# InterfaceBoard.net
KiCad netlist of a schematic drawn in Altium Designer
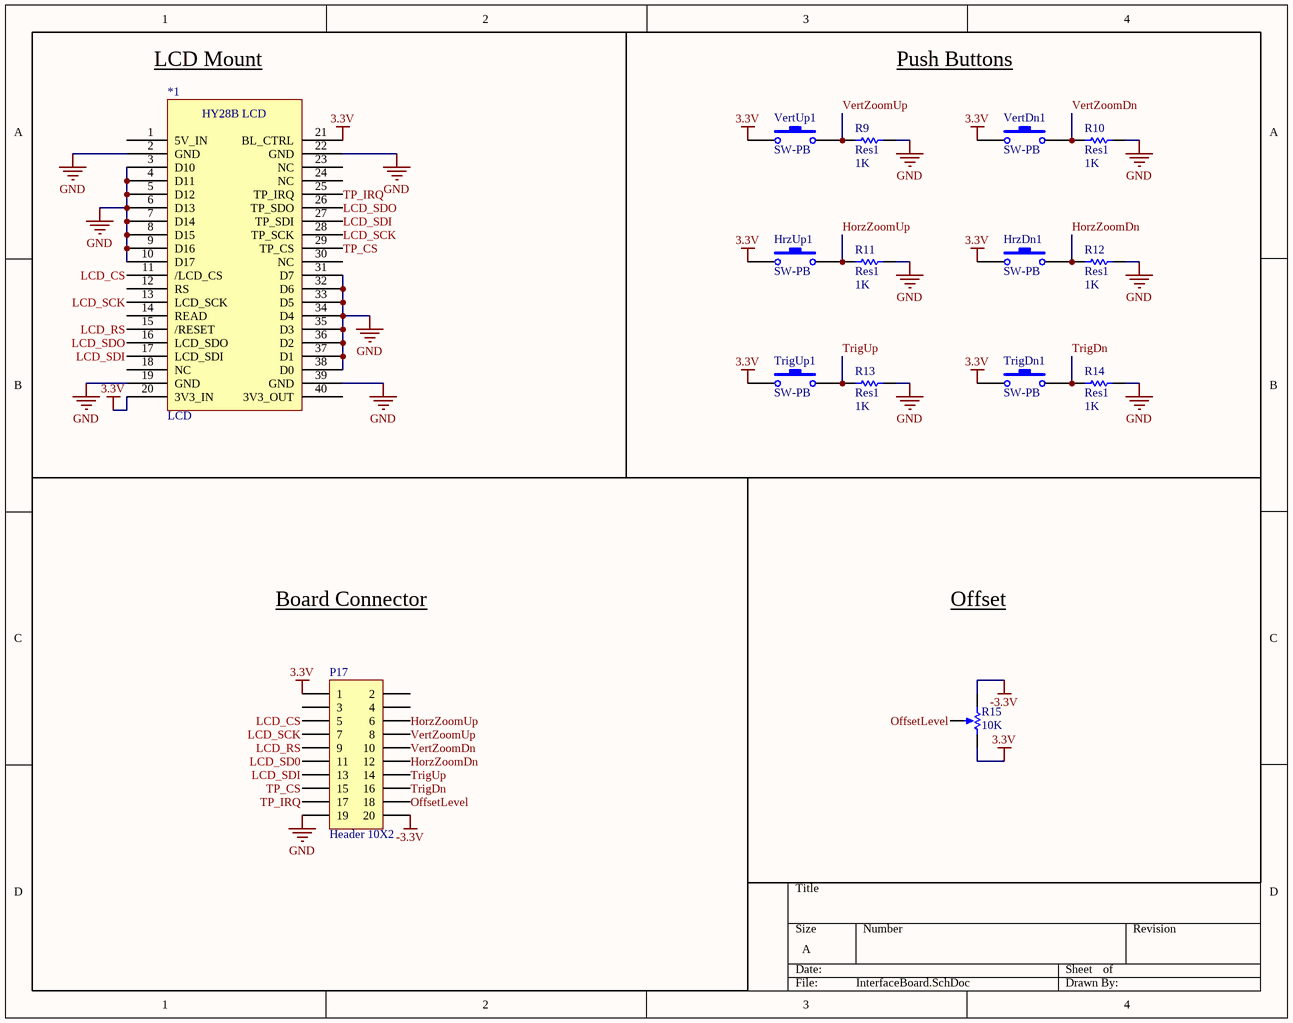
[diagram p0: InterfaceBoard.SchDoc]

(export (version "E")
  (design (tool "Eeschema 10.0.6"))
  (components
    (comp (ref "*1") (value "LCD") (footprint "LCD Footprint") (libsource (lib "MySchematics") (part "LCD")))
    (comp (ref "HrzDn1")
      (value "SW-PB")
      (footprint "SW PB")
      (description "DIGIKEY SW400-ND")
      (fields (field (name "PUBLISHER") "Altium Limited"))
      (libsource (lib "ECE LIB new") (part "SW-PB"))
    )
    (comp (ref "HrzUp1")
      (value "SW-PB")
      (footprint "SW PB")
      (description "DIGIKEY SW400-ND")
      (fields (field (name "PUBLISHER") "Altium Limited"))
      (libsource (lib "ECE LIB new") (part "SW-PB"))
    )
    (comp (ref "P17")
      (value "Header 10X2")
      (footprint "HDR2X10")
      (description "Header, 10-Pin, Dual row")
      (fields (field (name "PUBLISHER") "Altium Limited"))
      (libsource (lib "Miscellaneous Connectors") (part "Header 10X2"))
    )
    (comp (ref "R9")
      (value "Res1")
      (footprint "AXIAL-0.3")
      (description "Resistor")
      (fields (field (name "ALTIUM_VALUE") "1K") (field (name "PUBLISHER") "Altium Limited"))
      (libsource (lib "Miscellaneous Devices") (part "Res1"))
    )
    (comp (ref "R10")
      (value "Res1")
      (footprint "AXIAL-0.3")
      (description "Resistor")
      (fields (field (name "ALTIUM_VALUE") "1K") (field (name "PUBLISHER") "Altium Limited"))
      (libsource (lib "Miscellaneous Devices") (part "Res1"))
    )
    (comp (ref "R11")
      (value "Res1")
      (footprint "AXIAL-0.3")
      (description "Resistor")
      (fields (field (name "ALTIUM_VALUE") "1K") (field (name "PUBLISHER") "Altium Limited"))
      (libsource (lib "Miscellaneous Devices") (part "Res1"))
    )
    (comp (ref "R12")
      (value "Res1")
      (footprint "AXIAL-0.3")
      (description "Resistor")
      (fields (field (name "ALTIUM_VALUE") "1K") (field (name "PUBLISHER") "Altium Limited"))
      (libsource (lib "Miscellaneous Devices") (part "Res1"))
    )
    (comp (ref "R13")
      (value "Res1")
      (footprint "AXIAL-0.3")
      (description "Resistor")
      (fields (field (name "ALTIUM_VALUE") "1K") (field (name "PUBLISHER") "Altium Limited"))
      (libsource (lib "Miscellaneous Devices") (part "Res1"))
    )
    (comp (ref "R14")
      (value "Res1")
      (footprint "AXIAL-0.3")
      (description "Resistor")
      (fields (field (name "ALTIUM_VALUE") "1K") (field (name "PUBLISHER") "Altium Limited"))
      (libsource (lib "Miscellaneous Devices") (part "Res1"))
    )
    (comp (ref "R15")
      (value "10K")
      (footprint "BigPot")
      (description "Potentiometer")
      (fields (field (name "Comment") "RPot_3") (field (name "PUBLISHER") "Altium Limited"))
      (libsource (lib "ECE LIB new") (part "RPot"))
    )
    (comp (ref "TrigDn1")
      (value "SW-PB")
      (footprint "SW PB")
      (description "DIGIKEY SW400-ND")
      (fields (field (name "PUBLISHER") "Altium Limited"))
      (libsource (lib "ECE LIB new") (part "SW-PB"))
    )
    (comp (ref "TrigUp1")
      (value "SW-PB")
      (footprint "SW PB")
      (description "DIGIKEY SW400-ND")
      (fields (field (name "PUBLISHER") "Altium Limited"))
      (libsource (lib "ECE LIB new") (part "SW-PB"))
    )
    (comp (ref "VertDn1")
      (value "SW-PB")
      (footprint "SW PB")
      (description "DIGIKEY SW400-ND")
      (fields (field (name "PUBLISHER") "Altium Limited"))
      (libsource (lib "ECE LIB new") (part "SW-PB"))
    )
    (comp (ref "VertUp1")
      (value "SW-PB")
      (footprint "SW PB")
      (description "DIGIKEY SW400-ND")
      (fields (field (name "PUBLISHER") "Altium Limited"))
      (libsource (lib "ECE LIB new") (part "SW-PB"))
    )
  )
  (nets
    (net (code "1") (name "-3.3V") (class "Default")
      (node (ref "P17") (pin "20") (pinfunction "20_20") (pintype "passive"))
      (node (ref "R15") (pin "1") (pinfunction "TOP_1") (pintype "passive"))
    )
    (net (code "2") (name "/HorzZoomDn") (class "Default")
      (node (ref "HrzDn1") (pin "2") (pinfunction "2_2") (pintype "passive"))
      (node (ref "P17") (pin "12") (pinfunction "12_12") (pintype "passive"))
      (node (ref "R12") (pin "1") (pinfunction "1_1") (pintype "passive"))
    )
    (net (code "3") (name "/HorzZoomUp") (class "Default")
      (node (ref "HrzUp1") (pin "2") (pinfunction "2_2") (pintype "passive"))
      (node (ref "P17") (pin "6") (pinfunction "6_6") (pintype "passive"))
      (node (ref "R11") (pin "1") (pinfunction "1_1") (pintype "passive"))
    )
    (net (code "4") (name "/LCD_CS") (class "Default")
      (node (ref "*1") (pin "11") (pinfunction "/LCD_CS_11") (pintype "passive"))
      (node (ref "P17") (pin "5") (pinfunction "5_5") (pintype "passive"))
    )
    (net (code "5") (name "/LCD_RS") (class "Default")
      (node (ref "*1") (pin "15") (pinfunction "/RESET_15") (pintype "passive"))
      (node (ref "P17") (pin "9") (pinfunction "9_9") (pintype "passive"))
    )
    (net (code "6") (name "/LCD_SCK") (class "Default")
      (node (ref "*1") (pin "13") (pinfunction "LCD_SCK_13") (pintype "passive"))
      (node (ref "*1") (pin "28") (pinfunction "TP_SCK_28") (pintype "passive"))
      (node (ref "P17") (pin "7") (pinfunction "7_7") (pintype "passive"))
    )
    (net (code "7") (name "/LCD_SD0") (class "Default")
      (node (ref "P17") (pin "11") (pinfunction "11_11") (pintype "passive"))
    )
    (net (code "8") (name "/LCD_SDI") (class "Default")
      (node (ref "*1") (pin "17") (pinfunction "LCD_SDI_17") (pintype "passive"))
      (node (ref "*1") (pin "27") (pinfunction "TP_SDI_27") (pintype "passive"))
      (node (ref "P17") (pin "13") (pinfunction "13_13") (pintype "passive"))
    )
    (net (code "9") (name "/LCD_SDO") (class "Default")
      (node (ref "*1") (pin "16") (pinfunction "LCD_SDO_16") (pintype "passive"))
      (node (ref "*1") (pin "26") (pinfunction "TP_SDO_26") (pintype "passive"))
    )
    (net (code "10") (name "/OffsetLevel") (class "Default")
      (node (ref "P17") (pin "18") (pinfunction "18_18") (pintype "passive"))
      (node (ref "R15") (pin "2") (pinfunction "TAP_2") (pintype "passive"))
    )
    (net (code "11") (name "/TP_CS") (class "Default")
      (node (ref "*1") (pin "29") (pinfunction "TP_CS_29") (pintype "passive"))
      (node (ref "P17") (pin "15") (pinfunction "15_15") (pintype "passive"))
    )
    (net (code "12") (name "/TP_IRQ") (class "Default")
      (node (ref "*1") (pin "25") (pinfunction "TP_IRQ_25") (pintype "passive"))
      (node (ref "P17") (pin "17") (pinfunction "17_17") (pintype "passive"))
    )
    (net (code "13") (name "/TrigDn") (class "Default")
      (node (ref "P17") (pin "16") (pinfunction "16_16") (pintype "passive"))
      (node (ref "R14") (pin "1") (pinfunction "1_1") (pintype "passive"))
      (node (ref "TrigDn1") (pin "2") (pinfunction "2_2") (pintype "passive"))
    )
    (net (code "14") (name "/TrigUp") (class "Default")
      (node (ref "P17") (pin "14") (pinfunction "14_14") (pintype "passive"))
      (node (ref "R13") (pin "1") (pinfunction "1_1") (pintype "passive"))
      (node (ref "TrigUp1") (pin "2") (pinfunction "2_2") (pintype "passive"))
    )
    (net (code "15") (name "/VertZoomDn") (class "Default")
      (node (ref "P17") (pin "10") (pinfunction "10_10") (pintype "passive"))
      (node (ref "R10") (pin "1") (pinfunction "1_1") (pintype "passive"))
      (node (ref "VertDn1") (pin "2") (pinfunction "2_2") (pintype "passive"))
    )
    (net (code "16") (name "/VertZoomUp") (class "Default")
      (node (ref "P17") (pin "8") (pinfunction "8_8") (pintype "passive"))
      (node (ref "R9") (pin "1") (pinfunction "1_1") (pintype "passive"))
      (node (ref "VertUp1") (pin "2") (pinfunction "2_2") (pintype "passive"))
    )
    (net (code "17") (name "3.3V") (class "Default")
      (node (ref "*1") (pin "20") (pinfunction "3V3_IN_20") (pintype "passive"))
      (node (ref "*1") (pin "21") (pinfunction "BL_CTRL_21") (pintype "passive"))
      (node (ref "HrzDn1") (pin "1") (pinfunction "1_1") (pintype "passive"))
      (node (ref "HrzUp1") (pin "1") (pinfunction "1_1") (pintype "passive"))
      (node (ref "P17") (pin "1") (pinfunction "1_1") (pintype "passive"))
      (node (ref "R15") (pin "3") (pinfunction "BOT_3") (pintype "passive"))
      (node (ref "TrigDn1") (pin "1") (pinfunction "1_1") (pintype "passive"))
      (node (ref "TrigUp1") (pin "1") (pinfunction "1_1") (pintype "passive"))
      (node (ref "VertDn1") (pin "1") (pinfunction "1_1") (pintype "passive"))
      (node (ref "VertUp1") (pin "1") (pinfunction "1_1") (pintype "passive"))
    )
    (net (code "18") (name "GND") (class "Default")
      (node (ref "*1") (pin "10") (pinfunction "D17_10") (pintype "passive"))
      (node (ref "*1") (pin "19") (pinfunction "GND_19") (pintype "passive"))
      (node (ref "*1") (pin "2") (pinfunction "GND_2") (pintype "passive"))
      (node (ref "*1") (pin "22") (pinfunction "GND_22") (pintype "passive"))
      (node (ref "*1") (pin "3") (pinfunction "D10_3") (pintype "passive"))
      (node (ref "*1") (pin "31") (pinfunction "D7_31") (pintype "passive"))
      (node (ref "*1") (pin "32") (pinfunction "D6_32") (pintype "passive"))
      (node (ref "*1") (pin "33") (pinfunction "D5_33") (pintype "passive"))
      (node (ref "*1") (pin "34") (pinfunction "D4_34") (pintype "passive"))
      (node (ref "*1") (pin "35") (pinfunction "D3_35") (pintype "passive"))
      (node (ref "*1") (pin "36") (pinfunction "D2_36") (pintype "passive"))
      (node (ref "*1") (pin "37") (pinfunction "D1_37") (pintype "passive"))
      (node (ref "*1") (pin "38") (pinfunction "D0_38") (pintype "passive"))
      (node (ref "*1") (pin "39") (pinfunction "GND_39") (pintype "passive"))
      (node (ref "*1") (pin "4") (pinfunction "D11_4") (pintype "passive"))
      (node (ref "*1") (pin "5") (pinfunction "D12_5") (pintype "passive"))
      (node (ref "*1") (pin "6") (pinfunction "D13_6") (pintype "passive"))
      (node (ref "*1") (pin "7") (pinfunction "D14_7") (pintype "passive"))
      (node (ref "*1") (pin "8") (pinfunction "D15_8") (pintype "passive"))
      (node (ref "*1") (pin "9") (pinfunction "D16_9") (pintype "passive"))
      (node (ref "P17") (pin "19") (pinfunction "19_19") (pintype "passive"))
      (node (ref "R10") (pin "2") (pinfunction "2_2") (pintype "passive"))
      (node (ref "R11") (pin "2") (pinfunction "2_2") (pintype "passive"))
      (node (ref "R12") (pin "2") (pinfunction "2_2") (pintype "passive"))
      (node (ref "R13") (pin "2") (pinfunction "2_2") (pintype "passive"))
      (node (ref "R14") (pin "2") (pinfunction "2_2") (pintype "passive"))
      (node (ref "R9") (pin "2") (pinfunction "2_2") (pintype "passive"))
    )
    (net (code "19") (name "unconnected-(*1-3V3_OUT-Pad40)") (class "Default")
      (node (ref "*1") (pin "40") (pinfunction "3V3_OUT_40") (pintype "passive"))
    )
    (net (code "20") (name "unconnected-(*1-5V_IN-Pad1)") (class "Default")
      (node (ref "*1") (pin "1") (pinfunction "5V_IN_1") (pintype "passive"))
    )
    (net (code "21") (name "unconnected-(*1-NC-Pad18)") (class "Default")
      (node (ref "*1") (pin "18") (pinfunction "NC_18") (pintype "passive"))
    )
    (net (code "22") (name "unconnected-(*1-NC-Pad23)") (class "Default")
      (node (ref "*1") (pin "23") (pinfunction "NC_23") (pintype "passive"))
    )
    (net (code "23") (name "unconnected-(*1-NC-Pad24)") (class "Default")
      (node (ref "*1") (pin "24") (pinfunction "NC_24") (pintype "passive"))
    )
    (net (code "24") (name "unconnected-(*1-NC-Pad30)") (class "Default")
      (node (ref "*1") (pin "30") (pinfunction "NC_30") (pintype "passive"))
    )
    (net (code "25") (name "unconnected-(*1-READ-Pad14)") (class "Default")
      (node (ref "*1") (pin "14") (pinfunction "READ_14") (pintype "passive"))
    )
    (net (code "26") (name "unconnected-(*1-RS-Pad12)") (class "Default")
      (node (ref "*1") (pin "12") (pinfunction "RS_12") (pintype "passive"))
    )
    (net (code "27") (name "unconnected-(P17-Pad2)") (class "Default")
      (node (ref "P17") (pin "2") (pinfunction "2_2") (pintype "passive"))
    )
    (net (code "28") (name "unconnected-(P17-Pad3)") (class "Default")
      (node (ref "P17") (pin "3") (pinfunction "3_3") (pintype "passive"))
    )
    (net (code "29") (name "unconnected-(P17-Pad4)") (class "Default")
      (node (ref "P17") (pin "4") (pinfunction "4_4") (pintype "passive"))
    )
  )
)
